# sound.net
KiCad netlist of a schematic drawn in Altium Designer
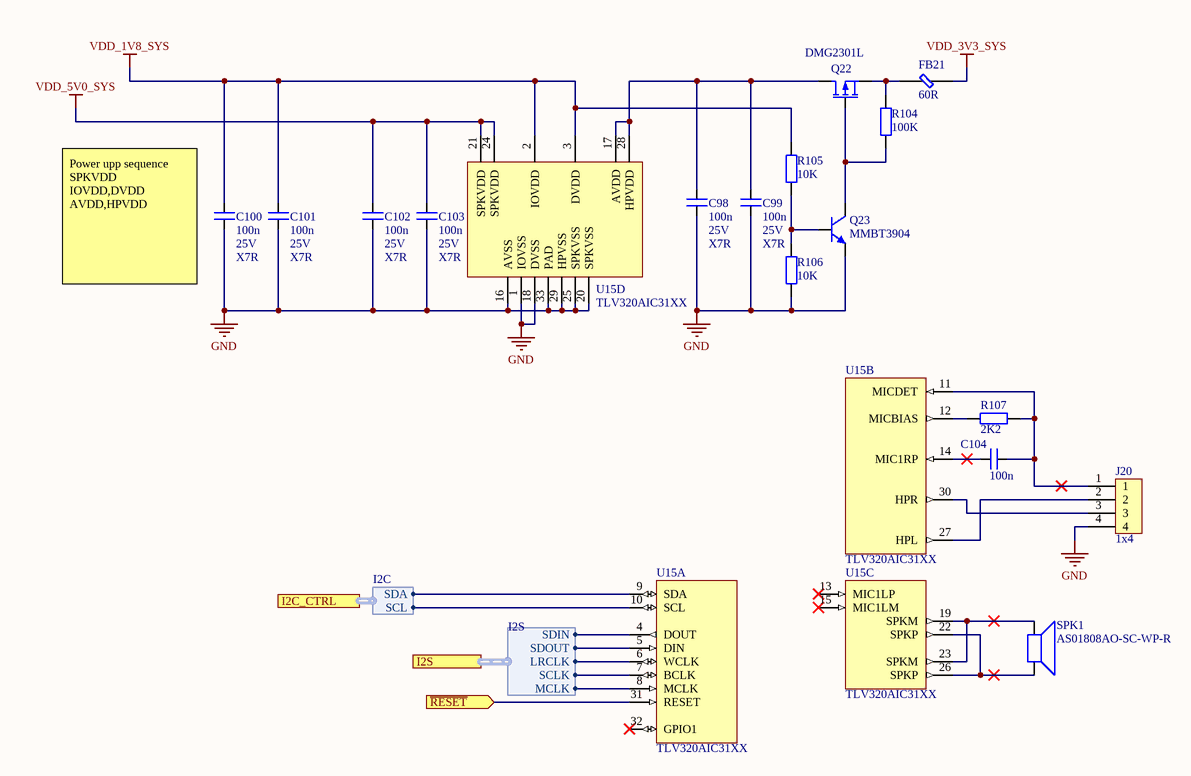
[diagram p0: sound.SchDoc]

(export (version "E")
  (design (tool "Eeschema 10.0.6"))
  (components
    (comp (ref "C98")
      (value "100n")
      (footprint "C1005[0402]")
      (description "Capacitor")
      (fields (field (name "VOLTAGE") "25V") (field (name "TYPE") "X7R") (field (name "Comment") "cap"))
      (libsource (lib "gpa_passives") (part "cap"))
    )
    (comp (ref "C99")
      (value "100n")
      (footprint "C1005[0402]")
      (description "Capacitor")
      (fields (field (name "VOLTAGE") "25V") (field (name "TYPE") "X7R") (field (name "Comment") "cap"))
      (libsource (lib "gpa_passives") (part "cap"))
    )
    (comp (ref "C100")
      (value "100n")
      (footprint "C1005[0402]")
      (description "Capacitor")
      (fields (field (name "VOLTAGE") "25V") (field (name "TYPE") "X7R") (field (name "Comment") "cap"))
      (libsource (lib "gpa_passives") (part "cap"))
    )
    (comp (ref "C101")
      (value "100n")
      (footprint "C1005[0402]")
      (description "Capacitor")
      (fields (field (name "VOLTAGE") "25V") (field (name "TYPE") "X7R") (field (name "Comment") "cap"))
      (libsource (lib "gpa_passives") (part "cap"))
    )
    (comp (ref "C102")
      (value "100n")
      (footprint "C1005[0402]")
      (description "Capacitor")
      (fields (field (name "VOLTAGE") "25V") (field (name "TYPE") "X7R") (field (name "Comment") "cap"))
      (libsource (lib "gpa_passives") (part "cap"))
    )
    (comp (ref "C103")
      (value "100n")
      (footprint "C1005[0402]")
      (description "Capacitor")
      (fields (field (name "VOLTAGE") "25V") (field (name "TYPE") "X7R") (field (name "Comment") "cap"))
      (libsource (lib "gpa_passives") (part "cap"))
    )
    (comp (ref "C104")
      (value "100n")
      (footprint "C1005[0402]")
      (description "Capacitor")
      (fields (field (name "VOLTAGE") "25V") (field (name "Comment") "cap"))
      (libsource (lib "gpa_passives") (part "cap"))
    )
    (comp (ref "FB21")
      (value "60R")
      (footprint "FBC1608X07N")
      (description "Ferrite bead")
      (libsource (lib "gpa_passives") (part "ferrite_bead"))
    )
    (comp (ref "J20")
      (value "1x4")
      (footprint "molex_picoblade_1x4")
      (libsource (lib "gpa_connectors") (part "header_1x4"))
    )
    (comp (ref "Q22")
      (value "DMG2301L")
      (footprint "NCH_SOT95P237X110-3N")
      (libsource (lib "gpa_actives") (part "pch_mosfet"))
    )
    (comp (ref "Q23")
      (value "MMBT3904")
      (footprint "NPN_SOT95P230X110-3N")
      (description "NPN Bipolar Transistor")
      (fields (field (name "PUBLISHER") "Altium Limited"))
      (libsource (lib "gpa_actives") (part "npn_bipolar"))
    )
    (comp (ref "R104")
      (value "100K")
      (footprint "R1005[0402]")
      (description "Resistor")
      (fields (field (name "Comment") "res"))
      (libsource (lib "gpa_passives") (part "res"))
    )
    (comp (ref "R105")
      (value "10K")
      (footprint "R1005[0402]")
      (description "Resistor")
      (fields (field (name "Comment") "res"))
      (libsource (lib "") (part "res_1"))
    )
    (comp (ref "R106")
      (value "10K")
      (footprint "R1005[0402]")
      (description "Resistor")
      (fields (field (name "Comment") "res"))
      (libsource (lib "") (part "res_3"))
    )
    (comp (ref "R107")
      (value "2K2")
      (footprint "R1005[0402]")
      (description "Resistor")
      (fields (field (name "Comment") "res"))
      (libsource (lib "") (part "res_2"))
    )
    (comp (ref "SPK1")
      (value "AS01808AO-SC-WP-R")
      (footprint "pui_audio_speaker")
      (libsource (lib "gpa_actives") (part "speaker"))
    )
    (comp (ref "U15")
      (value "TLV320AIC31XX")
      (footprint "TI_QFN50P500X500X100_HS-33M")
      (libsource (lib "gpa_ti") (part "tlv320aic3100"))
    )
  )
  (nets
    (net (code "3") (name "/LRCLK") (class "Default")
      (node (ref "U15") (pin "6") (pinfunction "WCLK_6") (pintype "bidirectional"))
    )
    (net (code "4") (name "/MCLK") (class "Default")
      (node (ref "U15") (pin "8") (pinfunction "MCLK_8") (pintype "input"))
    )
    (net (code "5") (name "/RESET") (class "Default")
      (node (ref "U15") (pin "31") (pinfunction "RESET_31") (pintype "input"))
    )
    (net (code "6") (name "/SCL") (class "Default")
      (node (ref "U15") (pin "10") (pinfunction "SCL_10") (pintype "bidirectional"))
    )
    (net (code "7") (name "/SCLK") (class "Default")
      (node (ref "U15") (pin "7") (pinfunction "BCLK_7") (pintype "bidirectional"))
    )
    (net (code "8") (name "/SDA") (class "Default")
      (node (ref "U15") (pin "9") (pinfunction "SDA_9") (pintype "bidirectional"))
    )
    (net (code "9") (name "/SDIN") (class "Default")
      (node (ref "U15") (pin "4") (pinfunction "DOUT_4") (pintype "output"))
    )
    (net (code "10") (name "/SDOUT") (class "Default")
      (node (ref "U15") (pin "5") (pinfunction "DIN_5") (pintype "input"))
    )
    (net (code "13") (name "GND") (class "Default")
      (node (ref "C100") (pin "1") (pinfunction "1_1") (pintype "passive"))
      (node (ref "C101") (pin "1") (pinfunction "1_1") (pintype "passive"))
      (node (ref "C102") (pin "1") (pinfunction "1_1") (pintype "passive"))
      (node (ref "C103") (pin "1") (pinfunction "1_1") (pintype "passive"))
      (node (ref "C98") (pin "1") (pinfunction "1_1") (pintype "passive"))
      (node (ref "C99") (pin "1") (pinfunction "1_1") (pintype "passive"))
      (node (ref "J20") (pin "4") (pinfunction "4_4") (pintype "passive"))
      (node (ref "Q23") (pin "E") (pinfunction "E_E") (pintype "passive"))
      (node (ref "R106") (pin "1") (pinfunction "1_1") (pintype "passive"))
      (node (ref "U15") (pin "1") (pinfunction "IOVSS_1") (pintype "power_in"))
      (node (ref "U15") (pin "16") (pinfunction "AVSS_16") (pintype "power_in"))
      (node (ref "U15") (pin "18") (pinfunction "DVSS_18") (pintype "power_in"))
      (node (ref "U15") (pin "20") (pinfunction "SPKVSS_20") (pintype "power_in"))
      (node (ref "U15") (pin "25") (pinfunction "SPKVSS_25") (pintype "power_in"))
      (node (ref "U15") (pin "29") (pinfunction "HPVSS_29") (pintype "power_in"))
      (node (ref "U15") (pin "33") (pinfunction "PAD_33") (pintype "power_in"))
    )
    (net (code "14") (name "Net-(FB21-Pad2)") (class "Default")
      (node (ref "FB21") (pin "2") (pinfunction "2_2") (pintype "passive"))
      (node (ref "Q22") (pin "S") (pinfunction "S_S") (pintype "passive"))
      (node (ref "R104") (pin "2") (pinfunction "2_2") (pintype "passive"))
    )
    (net (code "15") (name "Net-(Q22-PadG)") (class "Default")
      (node (ref "Q22") (pin "G") (pinfunction "G_G") (pintype "passive"))
      (node (ref "Q23") (pin "C") (pinfunction "C_C") (pintype "passive"))
      (node (ref "R104") (pin "1") (pinfunction "1_1") (pintype "passive"))
    )
    (net (code "16") (name "Net-(Q23-PadB)") (class "Default")
      (node (ref "Q23") (pin "B") (pinfunction "B_B") (pintype "passive"))
      (node (ref "R105") (pin "2") (pinfunction "2_2") (pintype "passive"))
      (node (ref "R106") (pin "2") (pinfunction "2_2") (pintype "passive"))
    )
    (net (code "17") (name "Net-(SPK1-Pad1)") (class "Default")
      (node (ref "SPK1") (pin "1") (pinfunction "1_1") (pintype "passive"))
      (node (ref "U15") (pin "19") (pinfunction "SPKM_19") (pintype "output"))
      (node (ref "U15") (pin "23") (pinfunction "SPKM_23") (pintype "output"))
    )
    (net (code "18") (name "Net-(SPK1-Pad2)") (class "Default")
      (node (ref "SPK1") (pin "2") (pinfunction "2_2") (pintype "passive"))
      (node (ref "U15") (pin "22") (pinfunction "SPKP_22") (pintype "output"))
      (node (ref "U15") (pin "26") (pinfunction "SPKP_26") (pintype "output"))
    )
    (net (code "19") (name "Net-(U15B-HPL)") (class "Default")
      (node (ref "J20") (pin "2") (pinfunction "2_2") (pintype "passive"))
      (node (ref "U15") (pin "27") (pinfunction "HPL_27") (pintype "output"))
    )
    (net (code "20") (name "Net-(U15B-HPR)") (class "Default")
      (node (ref "J20") (pin "3") (pinfunction "3_3") (pintype "passive"))
      (node (ref "U15") (pin "30") (pinfunction "HPR_30") (pintype "output"))
    )
    (net (code "21") (name "Net-(U15B-MIC1RP)") (class "Default")
      (node (ref "C104") (pin "1") (pinfunction "1_1") (pintype "passive"))
      (node (ref "U15") (pin "14") (pinfunction "MIC1RP_14") (pintype "input"))
    )
    (net (code "22") (name "Net-(U15B-MICBIAS)") (class "Default")
      (node (ref "R107") (pin "2") (pinfunction "2_2") (pintype "passive"))
      (node (ref "U15") (pin "12") (pinfunction "MICBIAS_12") (pintype "output"))
    )
    (net (code "23") (name "Net-(U15B-MICDET)") (class "Default")
      (node (ref "C104") (pin "2") (pinfunction "2_2") (pintype "passive"))
      (node (ref "J20") (pin "1") (pinfunction "1_1") (pintype "passive"))
      (node (ref "R107") (pin "1") (pinfunction "1_1") (pintype "passive"))
      (node (ref "U15") (pin "11") (pinfunction "MICDET_11") (pintype "input"))
    )
    (net (code "24") (name "Net-(U15D-AVDD)") (class "Default")
      (node (ref "C98") (pin "2") (pinfunction "2_2") (pintype "passive"))
      (node (ref "C99") (pin "2") (pinfunction "2_2") (pintype "passive"))
      (node (ref "Q22") (pin "D") (pinfunction "D_D") (pintype "passive"))
      (node (ref "U15") (pin "17") (pinfunction "AVDD_17") (pintype "power_in"))
      (node (ref "U15") (pin "28") (pinfunction "HPVDD_28") (pintype "power_in"))
    )
    (net (code "25") (name "VDD_1V8_SYS") (class "Default")
      (node (ref "C100") (pin "2") (pinfunction "2_2") (pintype "passive"))
      (node (ref "C101") (pin "2") (pinfunction "2_2") (pintype "passive"))
      (node (ref "R105") (pin "1") (pinfunction "1_1") (pintype "passive"))
      (node (ref "U15") (pin "2") (pinfunction "IOVDD_2") (pintype "power_in"))
      (node (ref "U15") (pin "3") (pinfunction "DVDD_3") (pintype "power_in"))
    )
    (net (code "26") (name "VDD_3V3_SYS") (class "Default")
      (node (ref "FB21") (pin "1") (pinfunction "1_1") (pintype "passive"))
    )
    (net (code "27") (name "VDD_5V0_SYS") (class "Default")
      (node (ref "C102") (pin "2") (pinfunction "2_2") (pintype "passive"))
      (node (ref "C103") (pin "2") (pinfunction "2_2") (pintype "passive"))
      (node (ref "U15") (pin "21") (pinfunction "SPKVDD_21") (pintype "power_in"))
      (node (ref "U15") (pin "24") (pinfunction "SPKVDD_24") (pintype "power_in"))
    )
    (net (code "28") (name "unconnected-(U15A-GPIO1-Pad32)") (class "Default")
      (node (ref "U15") (pin "32") (pinfunction "GPIO1_32") (pintype "bidirectional+no_connect"))
    )
    (net (code "29") (name "unconnected-(U15C-MIC1LM-Pad15)") (class "Default")
      (node (ref "U15") (pin "15") (pinfunction "MIC1LM_15") (pintype "input+no_connect"))
    )
    (net (code "30") (name "unconnected-(U15C-MIC1LP-Pad13)") (class "Default")
      (node (ref "U15") (pin "13") (pinfunction "MIC1LP_13") (pintype "input+no_connect"))
    )
  )
)
